# badge2017.net
KiCad netlist of a schematic drawn in EAGLE
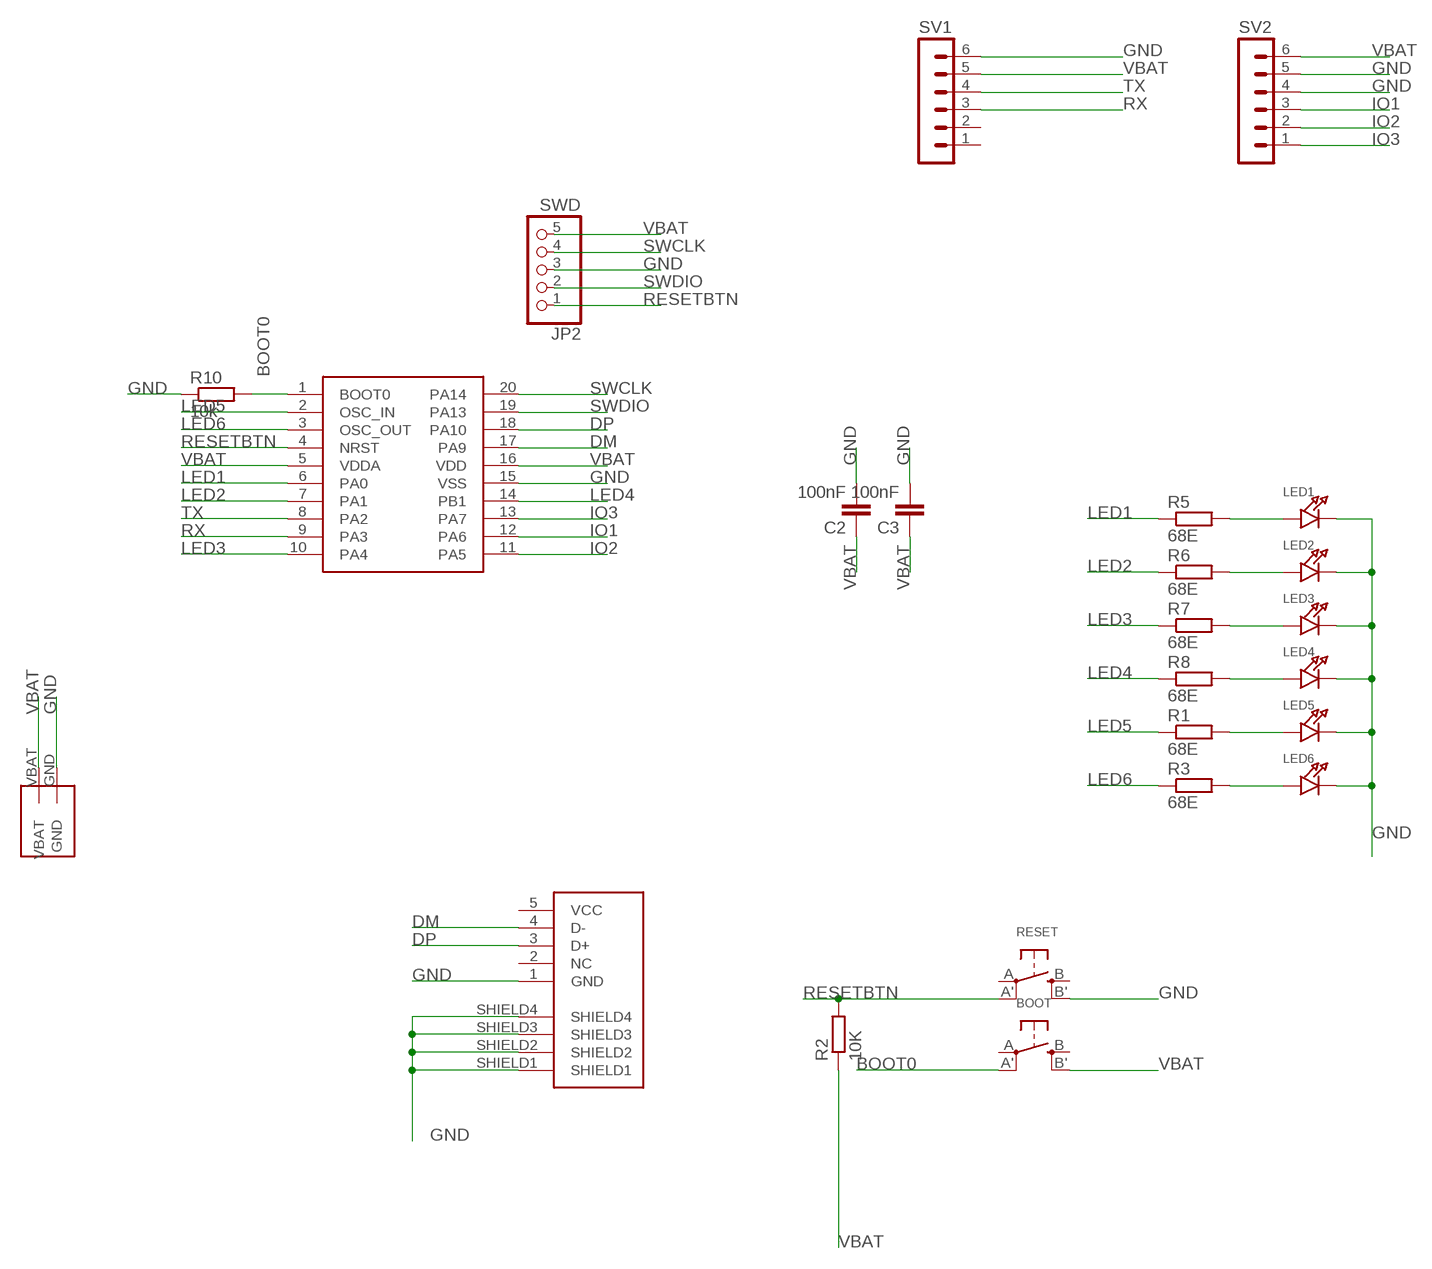
[diagram p0: schematic, sheet 1]

(export (version "E")
  (design (tool "Eeschema 10.0.6"))
  (components
    (comp (ref "BOOT")
      (value "SWITCH_TACT_SMT")
      (footprint "eagle-import:EVQ-Q2")
      (libsource (lib "eagle-import") (part "SWITCH_TACT_SMT"))
    )
    (comp (ref "C2")
      (value "100nF")
      (footprint "eagle-import:C0805")
      (libsource (lib "eagle-import") (part "C-EUC0805"))
    )
    (comp (ref "C3")
      (value "100nF")
      (footprint "eagle-import:C0805")
      (libsource (lib "eagle-import") (part "C-EUC0805"))
    )
    (comp (ref "JP2")
      (value "SWD")
      (footprint "eagle-import:1X05_OVAL")
      (libsource (lib "eagle-import") (part "HEADER-1X5"))
    )
    (comp (ref "LED1")
      (value "LED0805_NOOUTLINE")
      (footprint "eagle-import:CHIPLED_0805_NOOUTLINE")
      (libsource (lib "eagle-import") (part "LED0805_NOOUTLINE"))
    )
    (comp (ref "LED2")
      (value "LED0805_NOOUTLINE")
      (footprint "eagle-import:CHIPLED_0805_NOOUTLINE")
      (libsource (lib "eagle-import") (part "LED0805_NOOUTLINE"))
    )
    (comp (ref "LED3")
      (value "LED0805_NOOUTLINE")
      (footprint "eagle-import:CHIPLED_0805_NOOUTLINE")
      (libsource (lib "eagle-import") (part "LED0805_NOOUTLINE"))
    )
    (comp (ref "LED4")
      (value "LED0805_NOOUTLINE")
      (footprint "eagle-import:CHIPLED_0805_NOOUTLINE")
      (libsource (lib "eagle-import") (part "LED0805_NOOUTLINE"))
    )
    (comp (ref "LED5")
      (value "LED0805_NOOUTLINE")
      (footprint "eagle-import:CHIPLED_0805_NOOUTLINE")
      (libsource (lib "eagle-import") (part "LED0805_NOOUTLINE"))
    )
    (comp (ref "LED6")
      (value "LED0805_NOOUTLINE")
      (footprint "eagle-import:CHIPLED_0805_NOOUTLINE")
      (libsource (lib "eagle-import") (part "LED0805_NOOUTLINE"))
    )
    (comp (ref "R1")
      (value "68E")
      (footprint "eagle-import:R0805")
      (libsource (lib "eagle-import") (part "R-EU_R0805"))
    )
    (comp (ref "R2")
      (value "10K")
      (footprint "eagle-import:R0805")
      (libsource (lib "eagle-import") (part "R-EU_R0805"))
    )
    (comp (ref "R3")
      (value "68E")
      (footprint "eagle-import:R0805")
      (libsource (lib "eagle-import") (part "R-EU_R0805"))
    )
    (comp (ref "R5")
      (value "68E")
      (footprint "eagle-import:R0805")
      (libsource (lib "eagle-import") (part "R-EU_R0805"))
    )
    (comp (ref "R6")
      (value "68E")
      (footprint "eagle-import:R0805")
      (libsource (lib "eagle-import") (part "R-EU_R0805"))
    )
    (comp (ref "R7")
      (value "68E")
      (footprint "eagle-import:R0805")
      (libsource (lib "eagle-import") (part "R-EU_R0805"))
    )
    (comp (ref "R8")
      (value "68E")
      (footprint "eagle-import:R0805")
      (libsource (lib "eagle-import") (part "R-EU_R0805"))
    )
    (comp (ref "R10")
      (value "10k")
      (footprint "eagle-import:R0805")
      (libsource (lib "eagle-import") (part "R-EU_R0805"))
    )
    (comp (ref "RESET")
      (value "SWITCH_TACT_SMT")
      (footprint "eagle-import:EVQ-Q2")
      (libsource (lib "eagle-import") (part "SWITCH_TACT_SMT"))
    )
    (comp (ref "STM32")
      (value "STM32F030X4792-5925")
      (footprint "eagle-import:TSSOP20")
      (libsource (lib "eagle-import") (part "STM32F030X4792-5925"))
    )
    (comp (ref "SV1")
      (value "MA06-1")
      (footprint "eagle-import:MA06-1")
      (libsource (lib "eagle-import") (part "MA06-1"))
    )
    (comp (ref "SV2")
      (value "MA06-1")
      (footprint "eagle-import:MA06-1")
      (libsource (lib "eagle-import") (part "MA06-1"))
    )
    (comp (ref "U$1")
      (value "2AAPCBHOLDER")
      (footprint "eagle-import:2AAPCBBATTHOLDER")
      (libsource (lib "eagle-import") (part "2AAPCBHOLDER"))
    )
    (comp (ref "USB")
      (value "USBSOCK_MINI_SMD")
      (footprint "eagle-import:USBSOCK_MINI_SMD")
      (libsource (lib "eagle-import") (part "USBSOCK_MINI_SMD"))
    )
  )
  (nets
    (net (code "1") (name "/BOOT0") (class "Default")
      (node (ref "BOOT") (pin "A'") (pinfunction "P1_A'") (pintype "passive"))
      (node (ref "R10") (pin "2") (pinfunction "2_2") (pintype "passive"))
      (node (ref "STM32") (pin "1") (pinfunction "BOOT0_1") (pintype "bidirectional"))
    )
    (net (code "2") (name "/DM") (class "Default")
      (node (ref "STM32") (pin "17") (pinfunction "PA9_17") (pintype "bidirectional"))
      (node (ref "USB") (pin "4") (pinfunction "D-_4") (pintype "bidirectional"))
    )
    (net (code "3") (name "/DP") (class "Default")
      (node (ref "STM32") (pin "18") (pinfunction "PA10_18") (pintype "bidirectional"))
      (node (ref "USB") (pin "3") (pinfunction "D+_3") (pintype "bidirectional"))
    )
    (net (code "4") (name "/GND") (class "Default")
      (node (ref "C2") (pin "2") (pinfunction "2_2") (pintype "passive"))
      (node (ref "C3") (pin "2") (pinfunction "2_2") (pintype "passive"))
      (node (ref "JP2") (pin "3") (pinfunction "3_3") (pintype "passive"))
      (node (ref "LED1") (pin "C") (pinfunction "C_C") (pintype "passive"))
      (node (ref "LED2") (pin "C") (pinfunction "C_C") (pintype "passive"))
      (node (ref "LED3") (pin "C") (pinfunction "C_C") (pintype "passive"))
      (node (ref "LED4") (pin "C") (pinfunction "C_C") (pintype "passive"))
      (node (ref "LED5") (pin "C") (pinfunction "C_C") (pintype "passive"))
      (node (ref "LED6") (pin "C") (pinfunction "C_C") (pintype "passive"))
      (node (ref "R10") (pin "1") (pinfunction "1_1") (pintype "passive"))
      (node (ref "RESET") (pin "B'") (pinfunction "S1_B'") (pintype "passive"))
      (node (ref "STM32") (pin "15") (pinfunction "VSS_15") (pintype "bidirectional"))
      (node (ref "SV1") (pin "6") (pinfunction "6_6") (pintype "passive"))
      (node (ref "SV2") (pin "4") (pinfunction "4_4") (pintype "passive"))
      (node (ref "SV2") (pin "5") (pinfunction "5_5") (pintype "passive"))
      (node (ref "U$1") (pin "GND") (pinfunction "GND_GND") (pintype "bidirectional"))
      (node (ref "USB") (pin "1") (pinfunction "GND_1") (pintype "bidirectional"))
      (node (ref "USB") (pin "SHIELD1") (pinfunction "SHIELD1_SHIELD1") (pintype "bidirectional"))
      (node (ref "USB") (pin "SHIELD2") (pinfunction "SHIELD2_SHIELD2") (pintype "bidirectional"))
      (node (ref "USB") (pin "SHIELD3") (pinfunction "SHIELD3_SHIELD3") (pintype "bidirectional"))
      (node (ref "USB") (pin "SHIELD4") (pinfunction "SHIELD4_SHIELD4") (pintype "bidirectional"))
    )
    (net (code "5") (name "/IO1") (class "Default")
      (node (ref "STM32") (pin "12") (pinfunction "PA6_12") (pintype "bidirectional"))
      (node (ref "SV2") (pin "3") (pinfunction "3_3") (pintype "passive"))
    )
    (net (code "6") (name "/IO2") (class "Default")
      (node (ref "STM32") (pin "11") (pinfunction "PA5_11") (pintype "bidirectional"))
      (node (ref "SV2") (pin "2") (pinfunction "2_2") (pintype "passive"))
    )
    (net (code "7") (name "/IO3") (class "Default")
      (node (ref "STM32") (pin "13") (pinfunction "PA7_13") (pintype "bidirectional"))
      (node (ref "SV2") (pin "1") (pinfunction "1_1") (pintype "passive"))
    )
    (net (code "8") (name "/LED1") (class "Default")
      (node (ref "R5") (pin "1") (pinfunction "1_1") (pintype "passive"))
      (node (ref "STM32") (pin "6") (pinfunction "PA0_6") (pintype "bidirectional"))
    )
    (net (code "9") (name "/LED2") (class "Default")
      (node (ref "R6") (pin "1") (pinfunction "1_1") (pintype "passive"))
      (node (ref "STM32") (pin "7") (pinfunction "PA1_7") (pintype "bidirectional"))
    )
    (net (code "10") (name "/LED3") (class "Default")
      (node (ref "R7") (pin "1") (pinfunction "1_1") (pintype "passive"))
      (node (ref "STM32") (pin "10") (pinfunction "PA4_10") (pintype "bidirectional"))
    )
    (net (code "11") (name "/LED4") (class "Default")
      (node (ref "R8") (pin "1") (pinfunction "1_1") (pintype "passive"))
      (node (ref "STM32") (pin "14") (pinfunction "PB1_14") (pintype "bidirectional"))
    )
    (net (code "12") (name "/LED5") (class "Default")
      (node (ref "R1") (pin "1") (pinfunction "1_1") (pintype "passive"))
      (node (ref "STM32") (pin "2") (pinfunction "OSC_IN_2") (pintype "bidirectional"))
    )
    (net (code "13") (name "/LED6") (class "Default")
      (node (ref "R3") (pin "1") (pinfunction "1_1") (pintype "passive"))
      (node (ref "STM32") (pin "3") (pinfunction "OSC_OUT_3") (pintype "bidirectional"))
    )
    (net (code "14") (name "/RESETBTN") (class "Default")
      (node (ref "JP2") (pin "1") (pinfunction "1_1") (pintype "passive"))
      (node (ref "R2") (pin "2") (pinfunction "2_2") (pintype "passive"))
      (node (ref "RESET") (pin "A'") (pinfunction "P1_A'") (pintype "passive"))
      (node (ref "STM32") (pin "4") (pinfunction "NRST_4") (pintype "bidirectional"))
    )
    (net (code "15") (name "/RX") (class "Default")
      (node (ref "STM32") (pin "9") (pinfunction "PA3_9") (pintype "bidirectional"))
      (node (ref "SV1") (pin "3") (pinfunction "3_3") (pintype "passive"))
    )
    (net (code "16") (name "/SWCLK") (class "Default")
      (node (ref "JP2") (pin "4") (pinfunction "4_4") (pintype "passive"))
      (node (ref "STM32") (pin "20") (pinfunction "PA14_20") (pintype "bidirectional"))
    )
    (net (code "17") (name "/SWDIO") (class "Default")
      (node (ref "JP2") (pin "2") (pinfunction "2_2") (pintype "passive"))
      (node (ref "STM32") (pin "19") (pinfunction "PA13_19") (pintype "bidirectional"))
    )
    (net (code "18") (name "/TX") (class "Default")
      (node (ref "STM32") (pin "8") (pinfunction "PA2_8") (pintype "bidirectional"))
      (node (ref "SV1") (pin "4") (pinfunction "4_4") (pintype "passive"))
    )
    (net (code "19") (name "/VBAT") (class "Default")
      (node (ref "BOOT") (pin "B'") (pinfunction "S1_B'") (pintype "passive"))
      (node (ref "C2") (pin "1") (pinfunction "1_1") (pintype "passive"))
      (node (ref "C3") (pin "1") (pinfunction "1_1") (pintype "passive"))
      (node (ref "JP2") (pin "5") (pinfunction "5_5") (pintype "passive"))
      (node (ref "R2") (pin "1") (pinfunction "1_1") (pintype "passive"))
      (node (ref "STM32") (pin "16") (pinfunction "VDD_16") (pintype "bidirectional"))
      (node (ref "STM32") (pin "5") (pinfunction "VDDA_5") (pintype "bidirectional"))
      (node (ref "SV1") (pin "5") (pinfunction "5_5") (pintype "passive"))
      (node (ref "SV2") (pin "6") (pinfunction "6_6") (pintype "passive"))
      (node (ref "U$1") (pin "VBAT") (pinfunction "VBAT_VBAT") (pintype "bidirectional"))
    )
    (net (code "20") (name "Net-(LED1-PadA)") (class "Default")
      (node (ref "LED1") (pin "A") (pinfunction "A_A") (pintype "passive"))
      (node (ref "R5") (pin "2") (pinfunction "2_2") (pintype "passive"))
    )
    (net (code "21") (name "Net-(LED2-PadA)") (class "Default")
      (node (ref "LED2") (pin "A") (pinfunction "A_A") (pintype "passive"))
      (node (ref "R6") (pin "2") (pinfunction "2_2") (pintype "passive"))
    )
    (net (code "22") (name "Net-(LED3-PadA)") (class "Default")
      (node (ref "LED3") (pin "A") (pinfunction "A_A") (pintype "passive"))
      (node (ref "R7") (pin "2") (pinfunction "2_2") (pintype "passive"))
    )
    (net (code "23") (name "Net-(LED4-PadA)") (class "Default")
      (node (ref "LED4") (pin "A") (pinfunction "A_A") (pintype "passive"))
      (node (ref "R8") (pin "2") (pinfunction "2_2") (pintype "passive"))
    )
    (net (code "24") (name "Net-(LED5-PadA)") (class "Default")
      (node (ref "LED5") (pin "A") (pinfunction "A_A") (pintype "passive"))
      (node (ref "R1") (pin "2") (pinfunction "2_2") (pintype "passive"))
    )
    (net (code "25") (name "Net-(LED6-PadA)") (class "Default")
      (node (ref "LED6") (pin "A") (pinfunction "A_A") (pintype "passive"))
      (node (ref "R3") (pin "2") (pinfunction "2_2") (pintype "passive"))
    )
    (net (code "26") (name "unconnected-(BOOT-P-PadA)") (class "Default")
      (node (ref "BOOT") (pin "A") (pinfunction "P_A") (pintype "passive"))
    )
    (net (code "27") (name "unconnected-(BOOT-S-PadB)") (class "Default")
      (node (ref "BOOT") (pin "B") (pinfunction "S_B") (pintype "passive"))
    )
    (net (code "28") (name "unconnected-(RESET-P-PadA)") (class "Default")
      (node (ref "RESET") (pin "A") (pinfunction "P_A") (pintype "passive"))
    )
    (net (code "29") (name "unconnected-(RESET-S-PadB)") (class "Default")
      (node (ref "RESET") (pin "B") (pinfunction "S_B") (pintype "passive"))
    )
    (net (code "30") (name "unconnected-(SV1-Pad1)") (class "Default")
      (node (ref "SV1") (pin "1") (pinfunction "1_1") (pintype "passive"))
    )
    (net (code "31") (name "unconnected-(SV1-Pad2)") (class "Default")
      (node (ref "SV1") (pin "2") (pinfunction "2_2") (pintype "passive"))
    )
    (net (code "32") (name "unconnected-(USB-NC-Pad2)") (class "Default")
      (node (ref "USB") (pin "2") (pinfunction "NC_2") (pintype "bidirectional"))
    )
    (net (code "33") (name "unconnected-(USB-VCC-Pad5)") (class "Default")
      (node (ref "USB") (pin "5") (pinfunction "VCC_5") (pintype "bidirectional"))
    )
  )
)
